# ProPrj_Ozealis_2025-07-08.net
KiCad netlist of a schematic drawn in EasyEDA Pro
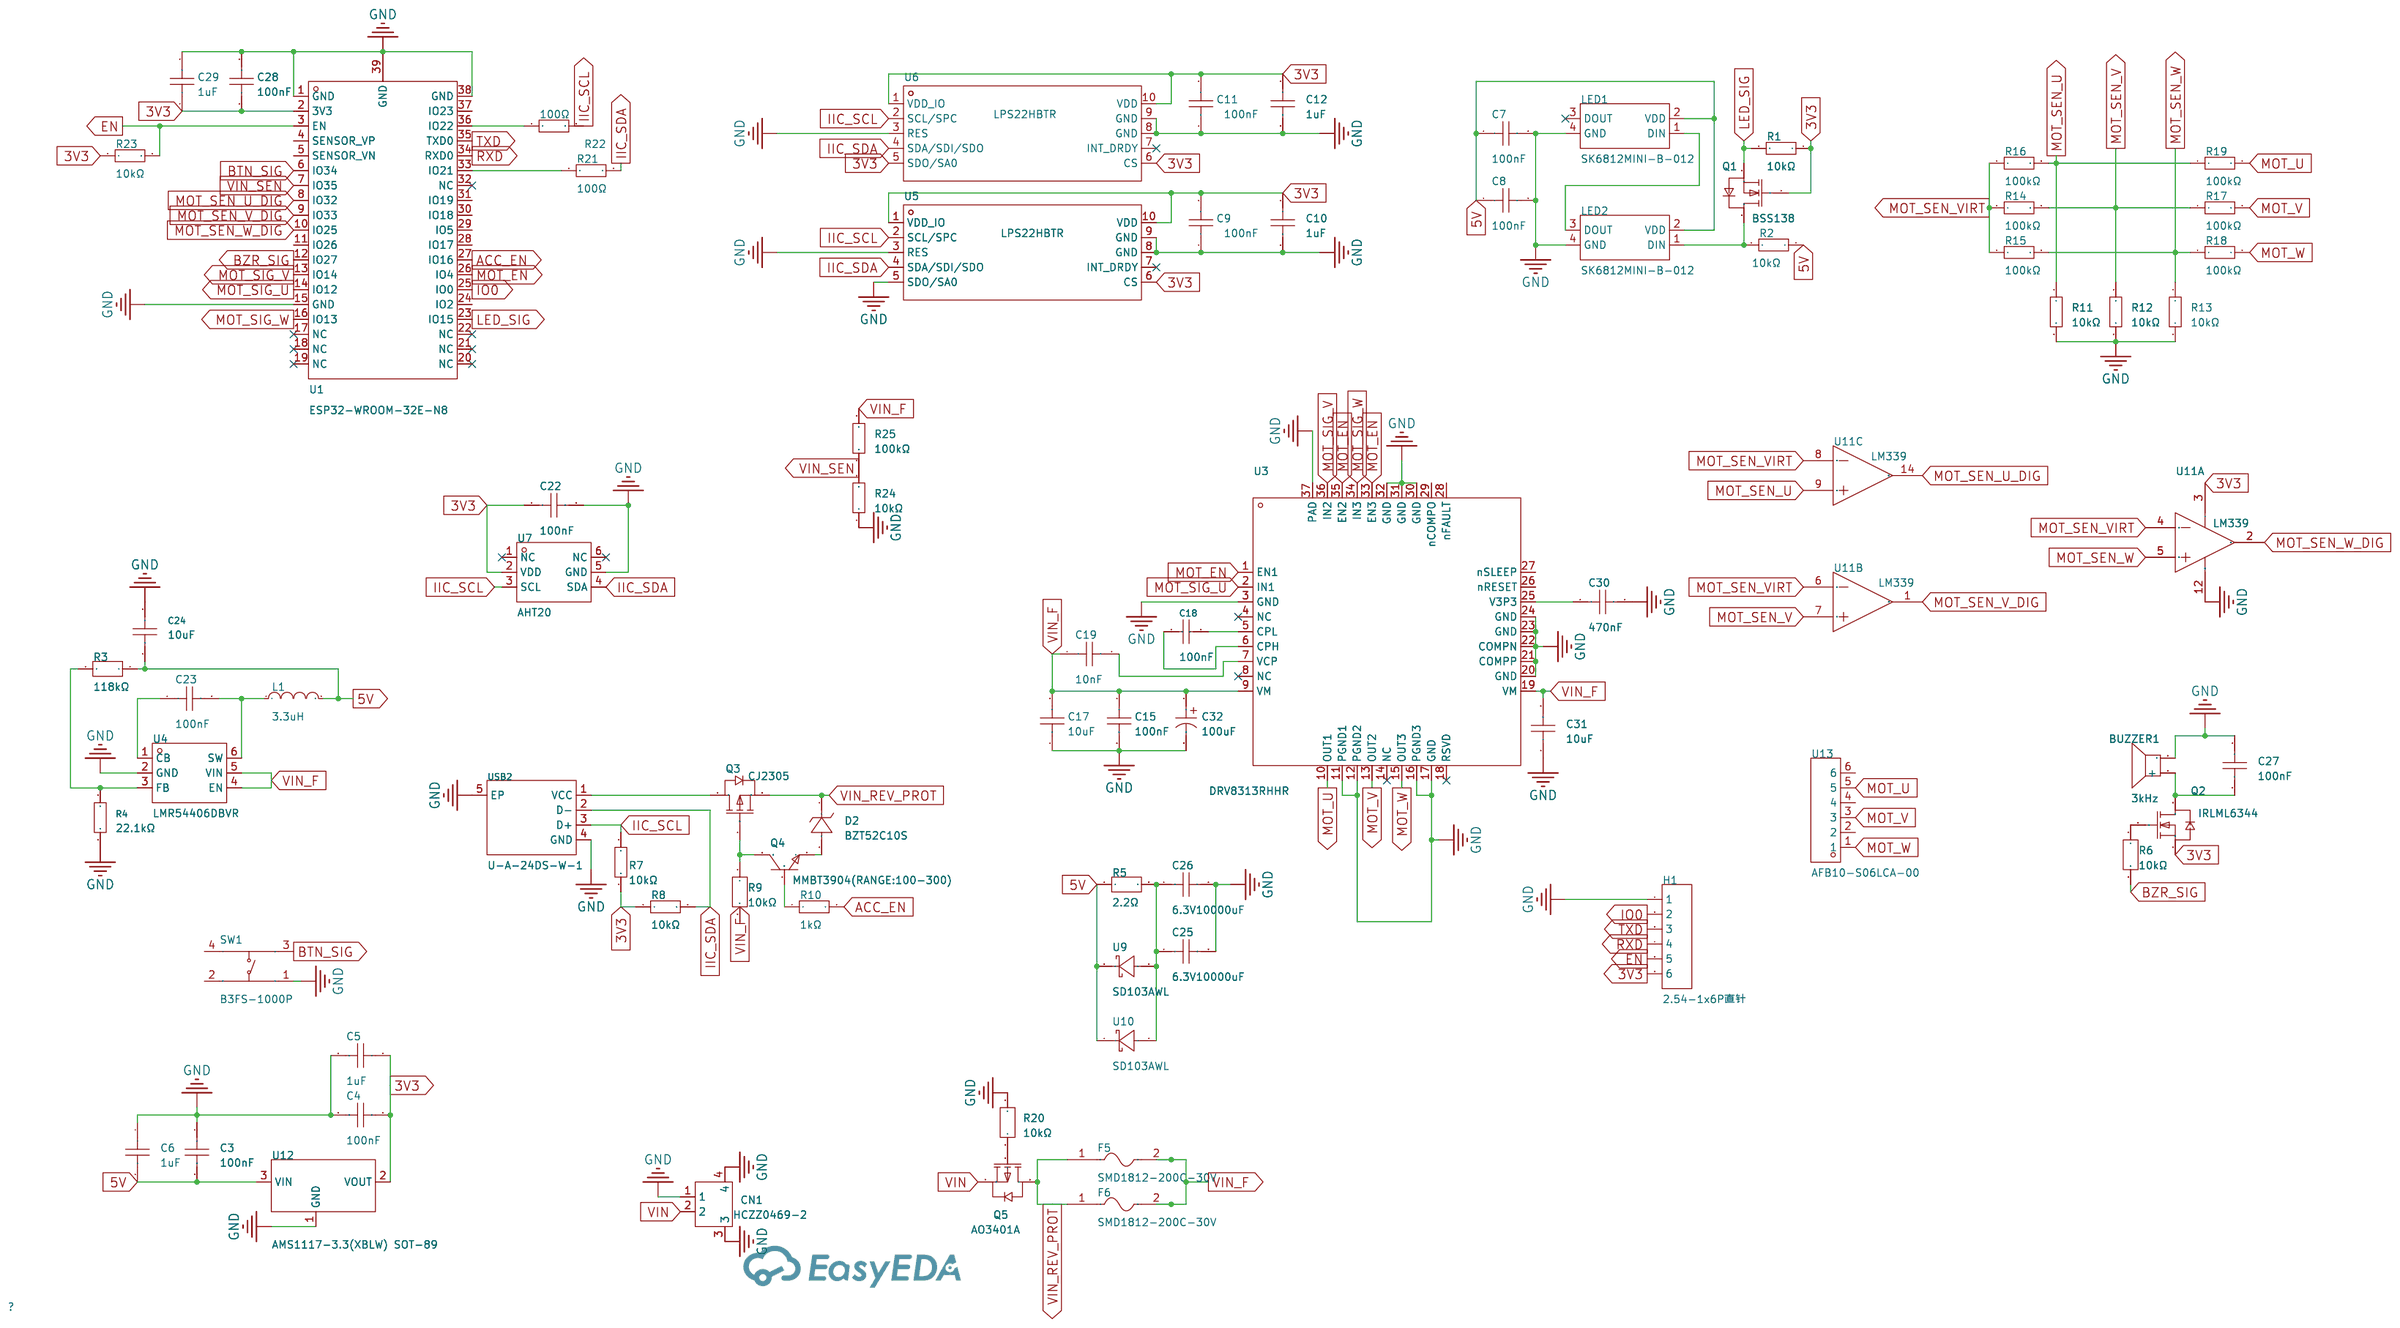
[diagram p0: schematic sheet]

(export (version "E")
  (design (tool "Eeschema 10.0.6"))
  (components
    (comp (ref "BUZZER1")
      (value "3kHz")
      (footprint "easyedapro:BUZ-SMD_L9.6-W9.6-LS10.0-R")
      (fields (field (name "Manufacturer Part") "FUET-9650B-3V") (field (name "Manufacturer") "FUET(福声科技)"))
      (libsource (lib "easyedapro") (part "FST-9650B-3V"))
    )
    (comp (ref "C3")
      (value "100nF")
      (footprint "easyedapro:C0603")
      (description "Capacitance:100nF Tolerance:±10% Tolerance:±10% Voltage Rating:50V Temperature Coefficient:X7R")
      (fields
        (field (name "Manufacturer Part") "CC0603KRX7R9BB104")
        (field (name "Manufacturer") "YAGEO(国巨)")
      )
      (libsource (lib "easyedapro") (part "CC0603KRX7R9BB104"))
    )
    (comp (ref "C4")
      (value "100nF")
      (footprint "easyedapro:C0603")
      (description "Capacitance:100nF Tolerance:±10% Tolerance:±10% Voltage Rating:50V Temperature Coefficient:X7R")
      (fields
        (field (name "Manufacturer Part") "CC0603KRX7R9BB104")
        (field (name "Manufacturer") "YAGEO(国巨)")
      )
      (libsource (lib "easyedapro") (part "CC0603KRX7R9BB104"))
    )
    (comp (ref "C5")
      (value "1uF")
      (footprint "easyedapro:C0603")
      (fields
        (field (name "Manufacturer Part") "CL10A105KB8NNNC")
        (field (name "Manufacturer") "SAMSUNG(三星)")
      )
      (libsource (lib "easyedapro") (part "CS1608Y5V105Z160NRB"))
    )
    (comp (ref "C6")
      (value "1uF")
      (footprint "easyedapro:C0603")
      (fields
        (field (name "Manufacturer Part") "CL10A105KB8NNNC")
        (field (name "Manufacturer") "SAMSUNG(三星)")
      )
      (libsource (lib "easyedapro") (part "CS1608Y5V105Z160NRB"))
    )
    (comp (ref "C7")
      (value "100nF")
      (footprint "easyedapro:C0603")
      (description "Capacitance:100nF Tolerance:±10% Tolerance:±10% Voltage Rating:50V Temperature Coefficient:X7R")
      (fields
        (field (name "Manufacturer Part") "CC0603KRX7R9BB104")
        (field (name "Manufacturer") "YAGEO(国巨)")
      )
      (libsource (lib "easyedapro") (part "CC0603KRX7R9BB104"))
    )
    (comp (ref "C8")
      (value "100nF")
      (footprint "easyedapro:C0603")
      (description "Capacitance:100nF Tolerance:±10% Tolerance:±10% Voltage Rating:50V Temperature Coefficient:X7R")
      (fields
        (field (name "Manufacturer Part") "CC0603KRX7R9BB104")
        (field (name "Manufacturer") "YAGEO(国巨)")
      )
      (libsource (lib "easyedapro") (part "CC0603KRX7R9BB104"))
    )
    (comp (ref "C9")
      (value "100nF")
      (footprint "easyedapro:C0603")
      (description "Capacitance:100nF Tolerance:±10% Tolerance:±10% Voltage Rating:50V Temperature Coefficient:X7R")
      (fields
        (field (name "Manufacturer Part") "CC0603KRX7R9BB104")
        (field (name "Manufacturer") "YAGEO(国巨)")
      )
      (libsource (lib "easyedapro") (part "CC0603KRX7R9BB104"))
    )
    (comp (ref "C10")
      (value "1uF")
      (footprint "easyedapro:C0603")
      (fields
        (field (name "Manufacturer Part") "CL10A105KB8NNNC")
        (field (name "Manufacturer") "SAMSUNG(三星)")
      )
      (libsource (lib "easyedapro") (part "CS1608Y5V105Z160NRB"))
    )
    (comp (ref "C11")
      (value "100nF")
      (footprint "easyedapro:C0603")
      (description "Capacitance:100nF Tolerance:±10% Tolerance:±10% Voltage Rating:50V Temperature Coefficient:X7R")
      (fields
        (field (name "Manufacturer Part") "CC0603KRX7R9BB104")
        (field (name "Manufacturer") "YAGEO(国巨)")
      )
      (libsource (lib "easyedapro") (part "CC0603KRX7R9BB104"))
    )
    (comp (ref "C12")
      (value "1uF")
      (footprint "easyedapro:C0603")
      (fields
        (field (name "Manufacturer Part") "CL10A105KB8NNNC")
        (field (name "Manufacturer") "SAMSUNG(三星)")
      )
      (libsource (lib "easyedapro") (part "CS1608Y5V105Z160NRB"))
    )
    (comp (ref "C15")
      (value "100nF")
      (footprint "easyedapro:C0603")
      (description "Capacitance:100nF Tolerance:±10% Tolerance:±10% Voltage Rating:50V Temperature Coefficient:X7R")
      (fields
        (field (name "Manufacturer Part") "CC0603KRX7R9BB104")
        (field (name "Manufacturer") "YAGEO(国巨)")
      )
      (libsource (lib "easyedapro") (part "CC0603KRX7R9BB104"))
    )
    (comp (ref "C17")
      (value "10uF")
      (footprint "easyedapro:C0805")
      (fields
        (field (name "Manufacturer Part") "GRM21BR61H106KE43L")
        (field (name "Manufacturer") "muRata(村田)")
      )
      (libsource (lib "easyedapro") (part "GRM21BR61H106KE43L"))
    )
    (comp (ref "C18")
      (value "100nF")
      (footprint "easyedapro:C0402")
      (description "Capacitance:100nF Tolerance:±10% Tolerance:±10% Voltage Rating:50V Temperature Coefficient:X7R")
      (fields
        (field (name "Manufacturer Part") "CC0603KRX7R9BB104")
        (field (name "Manufacturer") "YAGEO(国巨)")
      )
      (libsource (lib "easyedapro") (part "CC0402KRX7R9BB103"))
    )
    (comp (ref "C19")
      (value "10nF")
      (footprint "easyedapro:C0402")
      (description "Capacitance:10nF Tolerance:±10% Tolerance:±10% Voltage Rating:50V Temperature Coefficient:X7R")
      (fields (field (name "Manufacturer Part") "0603B103K500NT") (field (name "Manufacturer") "FH(风华)"))
      (libsource (lib "easyedapro") (part "FCC0402B104K160AT"))
    )
    (comp (ref "C22")
      (value "100nF")
      (footprint "easyedapro:C0603")
      (description "Capacitance:100nF Tolerance:±10% Tolerance:±10% Voltage Rating:50V Temperature Coefficient:X7R")
      (fields
        (field (name "Manufacturer Part") "CC0603KRX7R9BB104")
        (field (name "Manufacturer") "YAGEO(国巨)")
      )
      (libsource (lib "easyedapro") (part "CC0603KRX7R9BB104"))
    )
    (comp (ref "C23")
      (value "100nF")
      (footprint "easyedapro:C0603")
      (description "Capacitance:100nF Tolerance:±10% Tolerance:±10% Voltage Rating:50V Temperature Coefficient:X7R")
      (fields
        (field (name "Manufacturer Part") "CC0603KRX7R9BB104")
        (field (name "Manufacturer") "YAGEO(国巨)")
      )
      (libsource (lib "easyedapro") (part "CC0603KRX7R9BB104"))
    )
    (comp (ref "C24")
      (value "10uF")
      (footprint "easyedapro:C0603")
      (fields
        (field (name "Manufacturer Part") "TCC0603X5R106M6R3CT")
        (field (name "Manufacturer") "CCTC(三环)")
      )
      (libsource (lib "easyedapro") (part "TCC0603X5R106M6R3CT"))
    )
    (comp (ref "C25")
      (value "6.3V10000uF")
      (footprint "easyedapro:C0603")
      (libsource (lib "easyedapro") (part "CAP"))
    )
    (comp (ref "C26")
      (value "6.3V10000uF")
      (footprint "easyedapro:C0603")
      (libsource (lib "easyedapro") (part "CAP"))
    )
    (comp (ref "C27")
      (value "100nF")
      (footprint "easyedapro:C0603")
      (description "Capacitance:100nF Tolerance:±10% Tolerance:±10% Voltage Rating:50V Temperature Coefficient:X7R")
      (fields
        (field (name "Manufacturer Part") "CC0603KRX7R9BB104")
        (field (name "Manufacturer") "YAGEO(国巨)")
      )
      (libsource (lib "easyedapro") (part "CC0603KRX7R9BB104"))
    )
    (comp (ref "C28")
      (value "100nF")
      (footprint "easyedapro:C0603")
      (description "Capacitance:100nF Tolerance:±10% Tolerance:±10% Voltage Rating:50V Temperature Coefficient:X7R")
      (fields
        (field (name "Manufacturer Part") "CC0603KRX7R9BB104")
        (field (name "Manufacturer") "YAGEO(国巨)")
      )
      (libsource (lib "easyedapro") (part "CC0603KRX7R9BB104"))
    )
    (comp (ref "C29")
      (value "1uF")
      (footprint "easyedapro:C0603")
      (fields
        (field (name "Manufacturer Part") "CL10A105KB8NNNC")
        (field (name "Manufacturer") "SAMSUNG(三星)")
      )
      (libsource (lib "easyedapro") (part "CS1608Y5V105Z160NRB"))
    )
    (comp (ref "C30")
      (value "470nF")
      (footprint "easyedapro:C0603")
      (fields
        (field (name "Manufacturer Part") "CL10B474KA8NNNC")
        (field (name "Manufacturer") "SAMSUNG(三星)")
      )
      (libsource (lib "easyedapro") (part "CC0603KRX7R9BB474"))
    )
    (comp (ref "C31")
      (value "10uF")
      (footprint "easyedapro:C0805")
      (fields
        (field (name "Manufacturer Part") "GRM21BR61H106KE43L")
        (field (name "Manufacturer") "muRata(村田)")
      )
      (libsource (lib "easyedapro") (part "GRM21BR61H106KE43L"))
    )
    (comp (ref "C32")
      (value "100uF")
      (footprint "easyedapro:CAP-SMD_BD6.3-L6.6-W6.6-LS7.4-FD")
      (fields
        (field (name "Manufacturer Part") "RVT100UF35V67RV0034")
        (field (name "Manufacturer") "KNSCHA(科尼盛)")
      )
      (libsource (lib "easyedapro") (part "RVT100UF35V67RV0034"))
    )
    (comp (ref "CN1")
      (value "HCZZ0469-2")
      (footprint "easyedapro:CONN-SMD_2P-P2.00_HCZZ0469-2")
      (fields (field (name "Manufacturer") "HC(虹成电子)"))
      (libsource (lib "easyedapro") (part "HCZZ0469-2"))
    )
    (comp (ref "D2")
      (value "BZT52C10S")
      (footprint "easyedapro:SOD-323_L1.7-W1.3-LS2.6-RD")
      (fields (field (name "Manufacturer") "宏嘉诚"))
      (libsource (lib "easyedapro") (part "BZT52C10S_C19077446"))
    )
    (comp (ref "F5")
      (value "SMD1812-200C-30V")
      (footprint "easyedapro:F1812")
      (fields (field (name "Manufacturer") "BNstar(比诺星)"))
      (libsource (lib "easyedapro") (part "SMD1812-200C-30V"))
    )
    (comp (ref "F6")
      (value "SMD1812-200C-30V")
      (footprint "easyedapro:F1812")
      (fields (field (name "Manufacturer") "BNstar(比诺星)"))
      (libsource (lib "easyedapro") (part "SMD1812-200C-30V"))
    )
    (comp (ref "H1")
      (value "2.54-1x6P直针")
      (footprint "easyedapro:HDR-TH_6P-P2.54-V-M-1")
      (fields (field (name "Manufacturer") "BOOMELE(博穆精密)"))
      (libsource (lib "easyedapro") (part "Header-Male-2.54_1x6"))
    )
    (comp (ref "L1")
      (value "3.3uH")
      (footprint "easyedapro:IND-SMD_L3.0-W3.0_FNR30XXS")
      (fields (field (name "Manufacturer Part") "FNR3015S3R3MT") (field (name "Manufacturer") "cjiang(长江微电)"))
      (libsource (lib "easyedapro") (part "FNR3015S3R3MT"))
    )
    (comp (ref "LED1")
      (value "SK6812MINI-B-012")
      (footprint "easyedapro:LED-SMD_4P-L3.5-W3.5-R-SK6812MINI")
      (fields (field (name "Manufacturer") "欧思科光电"))
      (libsource (lib "easyedapro") (part "SK6812MINI-B-012"))
    )
    (comp (ref "LED2")
      (value "SK6812MINI-B-012")
      (footprint "easyedapro:LED-SMD_4P-L3.5-W3.5-R-SK6812MINI")
      (fields (field (name "Manufacturer") "欧思科光电"))
      (libsource (lib "easyedapro") (part "SK6812MINI-B-012"))
    )
    (comp (ref "Q1")
      (value "BSS138")
      (footprint "easyedapro:SOT-23-3_L2.9-W1.3-P1.90-LS2.4-BR-1")
      (fields (field (name "Manufacturer") "KUU"))
      (libsource (lib "easyedapro") (part "BSS138_C3015220"))
    )
    (comp (ref "Q2")
      (value "IRLML6344")
      (footprint "easyedapro:SOT-23-3_L3.0-W1.7-P0.95-LS2.9-BR")
      (fields (field (name "Manufacturer") "Hottech(合科泰)"))
      (libsource (lib "easyedapro") (part "IRLML6344"))
    )
    (comp (ref "Q3")
      (value "CJ2305")
      (footprint "easyedapro:SOT-23-3_L2.9-W1.3-P1.90-LS2.4-BR")
      (fields (field (name "Manufacturer") "CJ(江苏长电/长晶)"))
      (libsource (lib "easyedapro") (part "CJ2305"))
    )
    (comp (ref "Q4")
      (value "MMBT3904(RANGE:100-300)")
      (footprint "easyedapro:SOT-23-3_L2.9-W1.3-P1.90-LS2.4-BR")
      (fields (field (name "Manufacturer") "CJ(江苏长电/长晶)"))
      (libsource (lib "easyedapro") (part "MMBT3904"))
    )
    (comp (ref "Q5")
      (value "AO3401A")
      (footprint "easyedapro:SOT-23_L2.9-W1.3-P1.90-LS2.4-BR")
      (fields (field (name "Manufacturer") "UMW(友台半导体)"))
      (libsource (lib "easyedapro") (part "AO3401A_C347476"))
    )
    (comp (ref "R1")
      (value "10kΩ")
      (footprint "easyedapro:R0603")
      (fields (field (name "Manufacturer Part") "RC0603FR-0710KL") (field (name "Manufacturer") "YAGEO(国巨)"))
      (libsource (lib "easyedapro") (part "RC0603FR-0710KL"))
    )
    (comp (ref "R2")
      (value "10kΩ")
      (footprint "easyedapro:R0603")
      (fields (field (name "Manufacturer Part") "RC0603FR-0710KL") (field (name "Manufacturer") "YAGEO(国巨)"))
      (libsource (lib "easyedapro") (part "RC0603FR-0710KL"))
    )
    (comp (ref "R3")
      (value "118kΩ")
      (footprint "easyedapro:R0402")
      (fields (field (name "Manufacturer Part") "RC0402FR-07118KL") (field (name "Manufacturer") "YAGEO(国巨)"))
      (libsource (lib "easyedapro") (part "RC0402FR-07118KL"))
    )
    (comp (ref "R4")
      (value "22.1kΩ")
      (footprint "easyedapro:R0402")
      (fields
        (field (name "Manufacturer Part") "RMC040222.1K1%N")
        (field (name "Manufacturer") "Tyohm(幸亚电阻)")
      )
      (libsource (lib "easyedapro") (part "RMC040222.1K1%N"))
    )
    (comp (ref "R5")
      (value "2.2Ω")
      (footprint "easyedapro:R0603")
      (fields (field (name "Manufacturer Part") "FRC0603J2R2TS") (field (name "Manufacturer") "FOJAN(富捷)"))
      (libsource (lib "easyedapro") (part "FRC0603J2R2TS"))
    )
    (comp (ref "R6")
      (value "10kΩ")
      (footprint "easyedapro:R0603")
      (fields (field (name "Manufacturer Part") "FRC0603J103 TS") (field (name "Manufacturer") "FOJAN(富捷)"))
      (libsource (lib "easyedapro") (part "FRC0603J103TS"))
    )
    (comp (ref "R7")
      (value "10kΩ")
      (footprint "easyedapro:R0603")
      (fields (field (name "Manufacturer Part") "FRC0603J103 TS") (field (name "Manufacturer") "FOJAN(富捷)"))
      (libsource (lib "easyedapro") (part "RC0603FR-074K7L"))
    )
    (comp (ref "R8")
      (value "10kΩ")
      (footprint "easyedapro:R0603")
      (fields (field (name "Manufacturer Part") "FRC0603J103 TS") (field (name "Manufacturer") "FOJAN(富捷)"))
      (libsource (lib "easyedapro") (part "RC0603FR-074K7L"))
    )
    (comp (ref "R9")
      (value "10kΩ")
      (footprint "easyedapro:R0603")
      (fields (field (name "Manufacturer Part") "FRC0603J103 TS") (field (name "Manufacturer") "FOJAN(富捷)"))
      (libsource (lib "easyedapro") (part "FRC0603J103TS"))
    )
    (comp (ref "R10")
      (value "1kΩ")
      (footprint "easyedapro:R0603")
      (fields
        (field (name "Manufacturer Part") "0603WAF1001T5E")
        (field (name "Manufacturer") "UNI-ROYAL(厚声)")
      )
      (libsource (lib "easyedapro") (part "0603WAF1001T5E"))
    )
    (comp (ref "R11")
      (value "10kΩ")
      (footprint "easyedapro:R0603")
      (fields (field (name "Manufacturer Part") "RC0603FR-0710KL") (field (name "Manufacturer") "YAGEO(国巨)"))
      (libsource (lib "easyedapro") (part "RC0603FR-0710KL"))
    )
    (comp (ref "R12")
      (value "10kΩ")
      (footprint "easyedapro:R0603")
      (fields (field (name "Manufacturer Part") "RC0603FR-0710KL") (field (name "Manufacturer") "YAGEO(国巨)"))
      (libsource (lib "easyedapro") (part "RC0603FR-0710KL"))
    )
    (comp (ref "R13")
      (value "10kΩ")
      (footprint "easyedapro:R0603")
      (fields (field (name "Manufacturer Part") "RC0603FR-0710KL") (field (name "Manufacturer") "YAGEO(国巨)"))
      (libsource (lib "easyedapro") (part "RC0603FR-0710KL"))
    )
    (comp (ref "R14")
      (value "100kΩ")
      (footprint "easyedapro:R0603")
      (fields
        (field (name "Manufacturer Part") "0603WAF1003T5E")
        (field (name "Manufacturer") "UNI-ROYAL(厚声)")
      )
      (libsource (lib "easyedapro") (part "0603WAF1003T5E"))
    )
    (comp (ref "R15")
      (value "100kΩ")
      (footprint "easyedapro:R0603")
      (fields
        (field (name "Manufacturer Part") "0603WAF1003T5E")
        (field (name "Manufacturer") "UNI-ROYAL(厚声)")
      )
      (libsource (lib "easyedapro") (part "0603WAF1003T5E"))
    )
    (comp (ref "R16")
      (value "100kΩ")
      (footprint "easyedapro:R0603")
      (fields
        (field (name "Manufacturer Part") "0603WAF1003T5E")
        (field (name "Manufacturer") "UNI-ROYAL(厚声)")
      )
      (libsource (lib "easyedapro") (part "0603WAF1003T5E"))
    )
    (comp (ref "R17")
      (value "100kΩ")
      (footprint "easyedapro:R0603")
      (fields
        (field (name "Manufacturer Part") "0603WAF1003T5E")
        (field (name "Manufacturer") "UNI-ROYAL(厚声)")
      )
      (libsource (lib "easyedapro") (part "0603WAF1003T5E"))
    )
    (comp (ref "R18")
      (value "100kΩ")
      (footprint "easyedapro:R0603")
      (fields
        (field (name "Manufacturer Part") "0603WAF1003T5E")
        (field (name "Manufacturer") "UNI-ROYAL(厚声)")
      )
      (libsource (lib "easyedapro") (part "0603WAF1003T5E"))
    )
    (comp (ref "R19")
      (value "100kΩ")
      (footprint "easyedapro:R0603")
      (fields
        (field (name "Manufacturer Part") "0603WAF1003T5E")
        (field (name "Manufacturer") "UNI-ROYAL(厚声)")
      )
      (libsource (lib "easyedapro") (part "0603WAF1003T5E"))
    )
    (comp (ref "R20")
      (value "10kΩ")
      (footprint "easyedapro:R0603")
      (fields (field (name "Manufacturer Part") "FRC0603J103 TS") (field (name "Manufacturer") "FOJAN(富捷)"))
      (libsource (lib "easyedapro") (part "FRC0603J103TS"))
    )
    (comp (ref "R21")
      (value "100Ω")
      (footprint "easyedapro:R0603")
      (fields
        (field (name "Manufacturer Part") "0603WAF1000T5E")
        (field (name "Manufacturer") "UNI-ROYAL(厚声)")
      )
      (libsource (lib "easyedapro") (part "0603WAF1000T5E"))
    )
    (comp (ref "R22")
      (value "100Ω")
      (footprint "easyedapro:R0603")
      (fields
        (field (name "Manufacturer Part") "0603WAF1000T5E")
        (field (name "Manufacturer") "UNI-ROYAL(厚声)")
      )
      (libsource (lib "easyedapro") (part "0603WAF1000T5E"))
    )
    (comp (ref "R23")
      (value "10kΩ")
      (footprint "easyedapro:R0603")
      (fields (field (name "Manufacturer Part") "FRC0603J103 TS") (field (name "Manufacturer") "FOJAN(富捷)"))
      (libsource (lib "easyedapro") (part "RC0603FR-074K7L"))
    )
    (comp (ref "R24")
      (value "10kΩ")
      (footprint "easyedapro:R0603")
      (fields (field (name "Manufacturer Part") "FRC0603J103 TS") (field (name "Manufacturer") "FOJAN(富捷)"))
      (libsource (lib "easyedapro") (part "RC0603FR-074K7L"))
    )
    (comp (ref "R25")
      (value "100kΩ")
      (footprint "easyedapro:R0603")
      (fields
        (field (name "Manufacturer Part") "0603WAF1003T5E")
        (field (name "Manufacturer") "UNI-ROYAL(厚声)")
      )
      (libsource (lib "easyedapro") (part "0603WAF1003T5E"))
    )
    (comp (ref "SW1")
      (value "B3FS-1000P")
      (footprint "easyedapro:KEY-SMD_4P-L6.0-W6.3-P4.50-LS8.0")
      (fields (field (name "Manufacturer") "OMRON(欧姆龙)"))
      (libsource (lib "easyedapro") (part "B3FS-1000P"))
    )
    (comp (ref "U1")
      (value "ESP32-WROOM-32E-N8")
      (footprint "easyedapro:WIFI-SMD_ESP32-WROOM-32E")
      (fields (field (name "Manufacturer") "ESPRESSIF(乐鑫)"))
      (libsource (lib "easyedapro") (part "ESP32-WROOM-32E(8MB)"))
    )
    (comp (ref "U3")
      (value "DRV8313RHHR")
      (footprint "easyedapro:VQFN-36_L6.0-W6.0-P0.50-TL-EP")
      (fields (field (name "Manufacturer") "TI(德州仪器)"))
      (libsource (lib "easyedapro") (part "DRV8313RHHR"))
    )
    (comp (ref "U4")
      (value "LMR54406DBVR")
      (footprint "easyedapro:SOT-23-6_L2.9-W1.6-P0.95-LS2.8-BR")
      (fields (field (name "Manufacturer") "TI(德州仪器)"))
      (libsource (lib "easyedapro") (part "LMR54406DBVR"))
    )
    (comp (ref "U5")
      (value "LPS22HBTR")
      (footprint "easyedapro:HLGA-10L_LPS22HBTR")
      (fields (field (name "Manufacturer") "ST(意法半导体)"))
      (libsource (lib "easyedapro") (part "LPS22HBTR"))
    )
    (comp (ref "U6")
      (value "LPS22HBTR")
      (footprint "easyedapro:HLGA-10L_LPS22HBTR")
      (fields (field (name "Manufacturer") "ST(意法半导体)"))
      (libsource (lib "easyedapro") (part "LPS22HBTR"))
    )
    (comp (ref "U7")
      (value "AHT20")
      (footprint "easyedapro:SENSOR-SMD_L3.0-W3.0-P1.00-BR")
      (fields (field (name "Manufacturer") "广州奥松"))
      (libsource (lib "easyedapro") (part "AHT20_C2757850"))
    )
    (comp (ref "U9")
      (value "SD103AWL")
      (footprint "easyedapro:SOD-123FL_L2.8-W1.9-LS3.7-RD")
      (fields (field (name "Manufacturer") "GOODWORK(固得沃克)"))
      (libsource (lib "easyedapro") (part "SD103AWL"))
    )
    (comp (ref "U10")
      (value "SD103AWL")
      (footprint "easyedapro:SOD-123FL_L2.8-W1.9-LS3.7-RD")
      (fields (field (name "Manufacturer") "GOODWORK(固得沃克)"))
      (libsource (lib "easyedapro") (part "SD103AWL"))
    )
    (comp (ref "U11")
      (value "LM339")
      (footprint "easyedapro:SOIC-14_L8.7-W3.9-P1.27-LS6.0-BL")
      (fields (field (name "Manufacturer") "JSMSEMI(杰盛微)"))
      (libsource (lib "easyedapro") (part "LM339_C5456631"))
    )
    (comp (ref "U12")
      (value "AMS1117-3.3(XBLW) SOT-89")
      (footprint "easyedapro:SOT-89-3_L4.5-W2.5-P1.50-LS4.2-BR")
      (fields (field (name "Manufacturer") "XBLW(芯伯乐)"))
      (libsource (lib "easyedapro") (part "AMS1117-3.3(XBLW)"))
    )
    (comp (ref "U13")
      (value "AFB10-S06LCA-00")
      (footprint "easyedapro:FPC-SMD_6P-P1.00_AFB10-S6LCA-00")
      (fields (field (name "Manufacturer") "JS(钜硕电子)"))
      (libsource (lib "easyedapro") (part "AFB10-S06LCA-00"))
    )
    (comp (ref "USB2")
      (value "U-A-24DS-W-1")
      (footprint "easyedapro:USB-A-SMD_U-A-24DS-W-1.")
      (fields (field (name "Manufacturer") "韩国韩荣"))
      (libsource (lib "easyedapro") (part "U-A-24DS-W-1"))
    )
  )
  (nets
    (net (code "1") (name "3V3") (class "Default")
      (node (ref "C10") (pin "1") (pinfunction "1_1") (pintype "unspecified"))
      (node (ref "C11") (pin "2") (pinfunction "2_2") (pintype "unspecified"))
      (node (ref "C12") (pin "1") (pinfunction "1_1") (pintype "unspecified"))
      (node (ref "C22") (pin "1") (pinfunction "1_1") (pintype "unspecified"))
      (node (ref "C28") (pin "1") (pinfunction "1_1") (pintype "unspecified"))
      (node (ref "C29") (pin "1") (pinfunction "1_1") (pintype "unspecified"))
      (node (ref "C4") (pin "1") (pinfunction "1_1") (pintype "unspecified"))
      (node (ref "C5") (pin "1") (pinfunction "1_1") (pintype "unspecified"))
      (node (ref "C9") (pin "2") (pinfunction "2_2") (pintype "unspecified"))
      (node (ref "H1") (pin "6") (pinfunction "6_6") (pintype "input"))
      (node (ref "Q1") (pin "1") (pinfunction "G_1") (pintype "unspecified"))
      (node (ref "Q2") (pin "2") (pinfunction "S_2") (pintype "unspecified"))
      (node (ref "R1") (pin "1") (pinfunction "1_1") (pintype "input"))
      (node (ref "R23") (pin "1") (pinfunction "1_1") (pintype "input"))
      (node (ref "R7") (pin "1") (pinfunction "1_1") (pintype "input"))
      (node (ref "R8") (pin "1") (pinfunction "1_1") (pintype "input"))
      (node (ref "U1") (pin "2") (pinfunction "3V3_2") (pintype "unspecified"))
      (node (ref "U11") (pin "3") (pinfunction "V+_3") (pintype "unspecified"))
      (node (ref "U12") (pin "2") (pinfunction "VOUT_2") (pintype "unspecified"))
      (node (ref "U5") (pin "1") (pinfunction "VDD_IO_1") (pintype "unspecified"))
      (node (ref "U5") (pin "10") (pinfunction "VDD_10") (pintype "unspecified"))
      (node (ref "U5") (pin "6") (pinfunction "CS_6") (pintype "unspecified"))
      (node (ref "U6") (pin "1") (pinfunction "VDD_IO_1") (pintype "unspecified"))
      (node (ref "U6") (pin "10") (pinfunction "VDD_10") (pintype "unspecified"))
      (node (ref "U6") (pin "5") (pinfunction "SDO/SA0_5") (pintype "unspecified"))
      (node (ref "U6") (pin "6") (pinfunction "CS_6") (pintype "unspecified"))
      (node (ref "U7") (pin "2") (pinfunction "VDD_2") (pintype "unspecified"))
    )
    (net (code "2") (name "5V") (class "Default")
      (node (ref "C24") (pin "1") (pinfunction "1_1") (pintype "input"))
      (node (ref "C3") (pin "2") (pinfunction "2_2") (pintype "unspecified"))
      (node (ref "C6") (pin "2") (pinfunction "2_2") (pintype "unspecified"))
      (node (ref "C7") (pin "1") (pinfunction "1_1") (pintype "unspecified"))
      (node (ref "C8") (pin "1") (pinfunction "1_1") (pintype "unspecified"))
      (node (ref "L1") (pin "2") (pinfunction "2_2") (pintype "unspecified"))
      (node (ref "LED1") (pin "2") (pinfunction "VDD_2") (pintype "unspecified"))
      (node (ref "LED2") (pin "2") (pinfunction "VDD_2") (pintype "unspecified"))
      (node (ref "R2") (pin "1") (pinfunction "1_1") (pintype "input"))
      (node (ref "R3") (pin "1") (pinfunction "1_1") (pintype "unspecified"))
      (node (ref "R5") (pin "1") (pinfunction "1_1") (pintype "unspecified"))
      (node (ref "U10") (pin "1") (pinfunction "K_1") (pintype "unspecified"))
      (node (ref "U12") (pin "3") (pinfunction "VIN_3") (pintype "unspecified"))
      (node (ref "U9") (pin "1") (pinfunction "K_1") (pintype "unspecified"))
    )
    (net (code "3") (name "ACC_EN") (class "Default")
      (node (ref "R10") (pin "2") (pinfunction "2_2") (pintype "input"))
      (node (ref "U1") (pin "27") (pinfunction "IO16_27") (pintype "unspecified"))
    )
    (net (code "4") (name "BTN_SIG") (class "Default")
      (node (ref "SW1") (pin "3") (pinfunction "3_3") (pintype "unspecified"))
      (node (ref "U1") (pin "6") (pinfunction "IO34_6") (pintype "unspecified"))
    )
    (net (code "5") (name "BZR_SIG") (class "Default")
      (node (ref "R6") (pin "1") (pinfunction "1_1") (pintype "unspecified"))
      (node (ref "U1") (pin "12") (pinfunction "IO27_12") (pintype "unspecified"))
    )
    (net (code "6") (name "EN") (class "Default")
      (node (ref "H1") (pin "5") (pinfunction "5_5") (pintype "input"))
      (node (ref "R23") (pin "2") (pinfunction "2_2") (pintype "input"))
      (node (ref "U1") (pin "3") (pinfunction "EN_3") (pintype "unspecified"))
    )
    (net (code "7") (name "GND") (class "Default")
      (node (ref "BUZZER1") (pin "2") (pinfunction "2_2") (pintype "unspecified"))
      (node (ref "C10") (pin "2") (pinfunction "2_2") (pintype "unspecified"))
      (node (ref "C11") (pin "1") (pinfunction "1_1") (pintype "unspecified"))
      (node (ref "C12") (pin "2") (pinfunction "2_2") (pintype "unspecified"))
      (node (ref "C15") (pin "2") (pinfunction "2_2") (pintype "unspecified"))
      (node (ref "C17") (pin "1") (pinfunction "1_1") (pintype "unspecified"))
      (node (ref "C22") (pin "2") (pinfunction "2_2") (pintype "unspecified"))
      (node (ref "C24") (pin "2") (pinfunction "2_2") (pintype "input"))
      (node (ref "C25") (pin "2") (pinfunction "2_2") (pintype "input"))
      (node (ref "C26") (pin "2") (pinfunction "2_2") (pintype "input"))
      (node (ref "C27") (pin "1") (pinfunction "1_1") (pintype "unspecified"))
      (node (ref "C28") (pin "2") (pinfunction "2_2") (pintype "unspecified"))
      (node (ref "C29") (pin "2") (pinfunction "2_2") (pintype "unspecified"))
      (node (ref "C3") (pin "1") (pinfunction "1_1") (pintype "unspecified"))
      (node (ref "C30") (pin "2") (pinfunction "2_2") (pintype "unspecified"))
      (node (ref "C31") (pin "1") (pinfunction "1_1") (pintype "unspecified"))
      (node (ref "C32") (pin "2") (pinfunction "2_2") (pintype "input"))
      (node (ref "C4") (pin "2") (pinfunction "2_2") (pintype "unspecified"))
      (node (ref "C5") (pin "2") (pinfunction "2_2") (pintype "unspecified"))
      (node (ref "C6") (pin "1") (pinfunction "1_1") (pintype "unspecified"))
      (node (ref "C7") (pin "2") (pinfunction "2_2") (pintype "unspecified"))
      (node (ref "C8") (pin "2") (pinfunction "2_2") (pintype "unspecified"))
      (node (ref "C9") (pin "1") (pinfunction "1_1") (pintype "unspecified"))
      (node (ref "CN1") (pin "1") (pinfunction "1_1") (pintype "unspecified"))
      (node (ref "CN1") (pin "3") (pinfunction "3_3") (pintype "unspecified"))
      (node (ref "CN1") (pin "4") (pinfunction "4_4") (pintype "unspecified"))
      (node (ref "H1") (pin "1") (pinfunction "1_1") (pintype "input"))
      (node (ref "LED1") (pin "4") (pinfunction "GND_4") (pintype "unspecified"))
      (node (ref "LED2") (pin "4") (pinfunction "GND_4") (pintype "unspecified"))
      (node (ref "R11") (pin "2") (pinfunction "2_2") (pintype "input"))
      (node (ref "R12") (pin "2") (pinfunction "2_2") (pintype "input"))
      (node (ref "R13") (pin "2") (pinfunction "2_2") (pintype "input"))
      (node (ref "R20") (pin "2") (pinfunction "2_2") (pintype "unspecified"))
      (node (ref "R24") (pin "1") (pinfunction "1_1") (pintype "input"))
      (node (ref "R4") (pin "1") (pinfunction "1_1") (pintype "input"))
      (node (ref "SW1") (pin "1") (pinfunction "1_1") (pintype "unspecified"))
      (node (ref "U1") (pin "1") (pinfunction "GND_1") (pintype "unspecified"))
      (node (ref "U1") (pin "15") (pinfunction "GND_15") (pintype "unspecified"))
      (node (ref "U1") (pin "38") (pinfunction "GND_38") (pintype "unspecified"))
      (node (ref "U1") (pin "39") (pinfunction "GND_39") (pintype "unspecified"))
      (node (ref "U11") (pin "12") (pinfunction "GND_12") (pintype "unspecified"))
      (node (ref "U12") (pin "1") (pinfunction "GND_1") (pintype "unspecified"))
      (node (ref "U3") (pin "11") (pinfunction "PGND1_11") (pintype "unspecified"))
      (node (ref "U3") (pin "12") (pinfunction "PGND2_12") (pintype "unspecified"))
      (node (ref "U3") (pin "16") (pinfunction "PGND3_16") (pintype "unspecified"))
      (node (ref "U3") (pin "17") (pinfunction "GND_17") (pintype "unspecified"))
      (node (ref "U3") (pin "20") (pinfunction "GND_20") (pintype "unspecified"))
      (node (ref "U3") (pin "21") (pinfunction "COMPP_21") (pintype "unspecified"))
      (node (ref "U3") (pin "22") (pinfunction "COMPN_22") (pintype "unspecified"))
      (node (ref "U3") (pin "23") (pinfunction "GND_23") (pintype "unspecified"))
      (node (ref "U3") (pin "24") (pinfunction "GND_24") (pintype "unspecified"))
      (node (ref "U3") (pin "3") (pinfunction "GND_3") (pintype "unspecified"))
      (node (ref "U3") (pin "30") (pinfunction "GND_30") (pintype "unspecified"))
      (node (ref "U3") (pin "31") (pinfunction "GND_31") (pintype "unspecified"))
      (node (ref "U3") (pin "32") (pinfunction "GND_32") (pintype "unspecified"))
      (node (ref "U3") (pin "37") (pinfunction "PAD_37") (pintype "unspecified"))
      (node (ref "U4") (pin "2") (pinfunction "GND_2") (pintype "unspecified"))
      (node (ref "U5") (pin "3") (pinfunction "RES_3") (pintype "unspecified"))
      (node (ref "U5") (pin "5") (pinfunction "SDO/SA0_5") (pintype "unspecified"))
      (node (ref "U5") (pin "8") (pinfunction "GND_8") (pintype "unspecified"))
      (node (ref "U5") (pin "9") (pinfunction "GND_9") (pintype "unspecified"))
      (node (ref "U6") (pin "3") (pinfunction "RES_3") (pintype "unspecified"))
      (node (ref "U6") (pin "8") (pinfunction "GND_8") (pintype "unspecified"))
      (node (ref "U6") (pin "9") (pinfunction "GND_9") (pintype "unspecified"))
      (node (ref "U7") (pin "5") (pinfunction "GND_5") (pintype "unspecified"))
      (node (ref "USB2") (pin "4") (pinfunction "GND_4") (pintype "input"))
      (node (ref "USB2") (pin "5") (pinfunction "EP_5") (pintype "input"))
    )
    (net (code "8") (name "IIC_SCL") (class "Default")
      (node (ref "R22") (pin "2") (pinfunction "2_2") (pintype "input"))
      (node (ref "R7") (pin "2") (pinfunction "2_2") (pintype "input"))
      (node (ref "U5") (pin "2") (pinfunction "SCL/SPC_2") (pintype "unspecified"))
      (node (ref "U6") (pin "2") (pinfunction "SCL/SPC_2") (pintype "unspecified"))
      (node (ref "U7") (pin "3") (pinfunction "SCL_3") (pintype "unspecified"))
      (node (ref "USB2") (pin "3") (pinfunction "D+_3") (pintype "input"))
    )
    (net (code "9") (name "IIC_SDA") (class "Default")
      (node (ref "R21") (pin "2") (pinfunction "2_2") (pintype "input"))
      (node (ref "R8") (pin "2") (pinfunction "2_2") (pintype "input"))
      (node (ref "U5") (pin "4") (pinfunction "SDA/SDI/SDO_4") (pintype "unspecified"))
      (node (ref "U6") (pin "4") (pinfunction "SDA/SDI/SDO_4") (pintype "unspecified"))
      (node (ref "U7") (pin "4") (pinfunction "SDA_4") (pintype "unspecified"))
      (node (ref "USB2") (pin "2") (pinfunction "D-_2") (pintype "input"))
    )
    (net (code "10") (name "IO0") (class "Default")
      (node (ref "H1") (pin "2") (pinfunction "2_2") (pintype "input"))
      (node (ref "U1") (pin "25") (pinfunction "IO0_25") (pintype "unspecified"))
    )
    (net (code "11") (name "LED_SIG") (class "Default")
      (node (ref "Q1") (pin "2") (pinfunction "S_2") (pintype "unspecified"))
      (node (ref "R1") (pin "2") (pinfunction "2_2") (pintype "input"))
      (node (ref "U1") (pin "23") (pinfunction "IO15_23") (pintype "unspecified"))
    )
    (net (code "12") (name "MOT_EN") (class "Default")
      (node (ref "U1") (pin "26") (pinfunction "IO4_26") (pintype "unspecified"))
      (node (ref "U3") (pin "1") (pinfunction "EN1_1") (pintype "unspecified"))
      (node (ref "U3") (pin "33") (pinfunction "EN3_33") (pintype "unspecified"))
      (node (ref "U3") (pin "35") (pinfunction "EN2_35") (pintype "unspecified"))
    )
    (net (code "13") (name "MOT_SEN_U") (class "Default")
      (node (ref "R11") (pin "1") (pinfunction "1_1") (pintype "input"))
      (node (ref "R16") (pin "2") (pinfunction "2_2") (pintype "input"))
      (node (ref "R19") (pin "1") (pinfunction "1_1") (pintype "input"))
      (node (ref "U11") (pin "9") (pinfunction "IN3+_9") (pintype "unspecified"))
    )
    (net (code "14") (name "MOT_SEN_U_DIG") (class "Default")
      (node (ref "U1") (pin "8") (pinfunction "IO32_8") (pintype "unspecified"))
      (node (ref "U11") (pin "14") (pinfunction "OUT3_14") (pintype "unspecified"))
    )
    (net (code "15") (name "MOT_SEN_V") (class "Default")
      (node (ref "R12") (pin "1") (pinfunction "1_1") (pintype "input"))
      (node (ref "R14") (pin "2") (pinfunction "2_2") (pintype "input"))
      (node (ref "R17") (pin "1") (pinfunction "1_1") (pintype "input"))
      (node (ref "U11") (pin "7") (pinfunction "IN2+_7") (pintype "unspecified"))
    )
    (net (code "16") (name "MOT_SEN_VIRT") (class "Default")
      (node (ref "R14") (pin "1") (pinfunction "1_1") (pintype "input"))
      (node (ref "R15") (pin "1") (pinfunction "1_1") (pintype "input"))
      (node (ref "R16") (pin "1") (pinfunction "1_1") (pintype "input"))
      (node (ref "U11") (pin "4") (pinfunction "IN1-_4") (pintype "unspecified"))
      (node (ref "U11") (pin "6") (pinfunction "IN2-_6") (pintype "unspecified"))
      (node (ref "U11") (pin "8") (pinfunction "IN3-_8") (pintype "unspecified"))
    )
    (net (code "17") (name "MOT_SEN_V_DIG") (class "Default")
      (node (ref "U1") (pin "9") (pinfunction "IO33_9") (pintype "unspecified"))
      (node (ref "U11") (pin "1") (pinfunction "OUT2_1") (pintype "unspecified"))
    )
    (net (code "18") (name "MOT_SEN_W") (class "Default")
      (node (ref "R13") (pin "1") (pinfunction "1_1") (pintype "input"))
      (node (ref "R15") (pin "2") (pinfunction "2_2") (pintype "input"))
      (node (ref "R18") (pin "1") (pinfunction "1_1") (pintype "input"))
      (node (ref "U11") (pin "5") (pinfunction "IN1+_5") (pintype "unspecified"))
    )
    (net (code "19") (name "MOT_SEN_W_DIG") (class "Default")
      (node (ref "U1") (pin "10") (pinfunction "IO25_10") (pintype "unspecified"))
      (node (ref "U11") (pin "2") (pinfunction "OUT1_2") (pintype "unspecified"))
    )
    (net (code "20") (name "MOT_SIG_U") (class "Default")
      (node (ref "U1") (pin "14") (pinfunction "IO12_14") (pintype "unspecified"))
      (node (ref "U3") (pin "2") (pinfunction "IN1_2") (pintype "unspecified"))
    )
    (net (code "21") (name "MOT_SIG_V") (class "Default")
      (node (ref "U1") (pin "13") (pinfunction "IO14_13") (pintype "unspecified"))
      (node (ref "U3") (pin "36") (pinfunction "IN2_36") (pintype "unspecified"))
    )
    (net (code "22") (name "MOT_SIG_W") (class "Default")
      (node (ref "U1") (pin "16") (pinfunction "IO13_16") (pintype "unspecified"))
      (node (ref "U3") (pin "34") (pinfunction "IN3_34") (pintype "unspecified"))
    )
    (net (code "23") (name "MOT_U") (class "Default")
      (node (ref "R19") (pin "2") (pinfunction "2_2") (pintype "input"))
      (node (ref "U13") (pin "5") (pinfunction "5_5") (pintype "unspecified"))
      (node (ref "U3") (pin "10") (pinfunction "OUT1_10") (pintype "unspecified"))
    )
    (net (code "24") (name "MOT_V") (class "Default")
      (node (ref "R17") (pin "2") (pinfunction "2_2") (pintype "input"))
      (node (ref "U13") (pin "3") (pinfunction "3_3") (pintype "unspecified"))
      (node (ref "U3") (pin "13") (pinfunction "OUT2_13") (pintype "unspecified"))
    )
    (net (code "25") (name "MOT_W") (class "Default")
      (node (ref "R18") (pin "2") (pinfunction "2_2") (pintype "input"))
      (node (ref "U13") (pin "1") (pinfunction "1_1") (pintype "unspecified"))
      (node (ref "U3") (pin "15") (pinfunction "OUT3_15") (pintype "unspecified"))
    )
    (net (code "26") (name "Net-(BUZZER1-+)") (class "Default")
      (node (ref "BUZZER1") (pin "1") (pinfunction "+_1") (pintype "unspecified"))
      (node (ref "C27") (pin "2") (pinfunction "2_2") (pintype "unspecified"))
      (node (ref "Q2") (pin "3") (pinfunction "D_3") (pintype "unspecified"))
    )
    (net (code "27") (name "Net-(D2-A)") (class "Default")
      (node (ref "D2") (pin "2") (pinfunction "A_2") (pintype "unspecified"))
      (node (ref "Q4") (pin "2") (pinfunction "E_2") (pintype "unspecified"))
    )
    (net (code "28") (name "Net-(LED1-DIN)") (class "Default")
      (node (ref "LED1") (pin "1") (pinfunction "DIN_1") (pintype "unspecified"))
      (node (ref "LED2") (pin "3") (pinfunction "DOUT_3") (pintype "unspecified"))
    )
    (net (code "29") (name "Net-(LED2-DIN)") (class "Default")
      (node (ref "LED2") (pin "1") (pinfunction "DIN_1") (pintype "unspecified"))
      (node (ref "Q1") (pin "3") (pinfunction "D_3") (pintype "unspecified"))
      (node (ref "R2") (pin "2") (pinfunction "2_2") (pintype "input"))
    )
    (net (code "30") (name "Net-(Q2-G)") (class "Default")
      (node (ref "Q2") (pin "1") (pinfunction "G_1") (pintype "unspecified"))
      (node (ref "R6") (pin "2") (pinfunction "2_2") (pintype "unspecified"))
    )
    (net (code "31") (name "Net-(Q3-D)") (class "Default")
      (node (ref "Q3") (pin "3") (pinfunction "D_3") (pintype "unspecified"))
      (node (ref "USB2") (pin "1") (pinfunction "VCC_1") (pintype "input"))
    )
    (net (code "32") (name "Net-(Q3-G)") (class "Default")
      (node (ref "Q3") (pin "1") (pinfunction "G_1") (pintype "unspecified"))
      (node (ref "Q4") (pin "3") (pinfunction "C_3") (pintype "unspecified"))
      (node (ref "R9") (pin "1") (pinfunction "1_1") (pintype "unspecified"))
    )
    (net (code "33") (name "Net-(Q4-B)") (class "Default")
      (node (ref "Q4") (pin "1") (pinfunction "B_1") (pintype "unspecified"))
      (node (ref "R10") (pin "1") (pinfunction "1_1") (pintype "input"))
    )
    (net (code "34") (name "Net-(Q5-G)") (class "Default")
      (node (ref "Q5") (pin "1") (pinfunction "G_1") (pintype "unspecified"))
      (node (ref "R20") (pin "1") (pinfunction "1_1") (pintype "unspecified"))
    )
    (net (code "35") (name "Net-(U1-IO21)") (class "Default")
      (node (ref "R21") (pin "1") (pinfunction "1_1") (pintype "input"))
      (node (ref "U1") (pin "33") (pinfunction "IO21_33") (pintype "unspecified"))
    )
    (net (code "36") (name "Net-(U1-IO22)") (class "Default")
      (node (ref "R22") (pin "1") (pinfunction "1_1") (pintype "input"))
      (node (ref "U1") (pin "36") (pinfunction "IO22_36") (pintype "unspecified"))
    )
    (net (code "37") (name "Net-(U3-CPH)") (class "Default")
      (node (ref "C18") (pin "1") (pinfunction "1_1") (pintype "input"))
      (node (ref "U3") (pin "6") (pinfunction "CPH_6") (pintype "unspecified"))
    )
    (net (code "38") (name "Net-(U3-CPL)") (class "Default")
      (node (ref "C18") (pin "2") (pinfunction "2_2") (pintype "input"))
      (node (ref "U3") (pin "5") (pinfunction "CPL_5") (pintype "unspecified"))
    )
    (net (code "39") (name "Net-(U3-V3P3)") (class "Default")
      (node (ref "C30") (pin "1") (pinfunction "1_1") (pintype "unspecified"))
      (node (ref "U3") (pin "25") (pinfunction "V3P3_25") (pintype "unspecified"))
    )
    (net (code "40") (name "Net-(U3-VCP)") (class "Default")
      (node (ref "C19") (pin "2") (pinfunction "2_2") (pintype "unspecified"))
      (node (ref "U3") (pin "7") (pinfunction "VCP_7") (pintype "unspecified"))
    )
    (net (code "41") (name "Net-(U4-CB)") (class "Default")
      (node (ref "C23") (pin "1") (pinfunction "1_1") (pintype "unspecified"))
      (node (ref "U4") (pin "1") (pinfunction "CB_1") (pintype "unspecified"))
    )
    (net (code "42") (name "Net-(U4-FB)") (class "Default")
      (node (ref "R3") (pin "2") (pinfunction "2_2") (pintype "unspecified"))
      (node (ref "R4") (pin "2") (pinfunction "2_2") (pintype "input"))
      (node (ref "U4") (pin "3") (pinfunction "FB_3") (pintype "unspecified"))
    )
    (net (code "43") (name "Net-(U4-SW)") (class "Default")
      (node (ref "C23") (pin "2") (pinfunction "2_2") (pintype "unspecified"))
      (node (ref "L1") (pin "1") (pinfunction "1_1") (pintype "unspecified"))
      (node (ref "U4") (pin "6") (pinfunction "SW_6") (pintype "unspecified"))
    )
    (net (code "44") (name "Net-(U10-A)") (class "Default")
      (node (ref "C25") (pin "1") (pinfunction "1_1") (pintype "input"))
      (node (ref "C26") (pin "1") (pinfunction "1_1") (pintype "input"))
      (node (ref "R5") (pin "2") (pinfunction "2_2") (pintype "unspecified"))
      (node (ref "U10") (pin "2") (pinfunction "A_2") (pintype "unspecified"))
      (node (ref "U9") (pin "2") (pinfunction "A_2") (pintype "unspecified"))
    )
    (net (code "45") (name "RXD") (class "Default")
      (node (ref "H1") (pin "4") (pinfunction "4_4") (pintype "input"))
      (node (ref "U1") (pin "34") (pinfunction "RXD0_34") (pintype "unspecified"))
    )
    (net (code "46") (name "TXD") (class "Default")
      (node (ref "H1") (pin "3") (pinfunction "3_3") (pintype "input"))
      (node (ref "U1") (pin "35") (pinfunction "TXD0_35") (pintype "unspecified"))
    )
    (net (code "47") (name "VIN") (class "Default")
      (node (ref "CN1") (pin "2") (pinfunction "2_2") (pintype "unspecified"))
      (node (ref "Q5") (pin "2") (pinfunction "S_2") (pintype "unspecified"))
    )
    (net (code "48") (name "VIN_F") (class "Default")
      (node (ref "C15") (pin "1") (pinfunction "1_1") (pintype "unspecified"))
      (node (ref "C17") (pin "2") (pinfunction "2_2") (pintype "unspecified"))
      (node (ref "C19") (pin "1") (pinfunction "1_1") (pintype "unspecified"))
      (node (ref "C31") (pin "2") (pinfunction "2_2") (pintype "unspecified"))
      (node (ref "C32") (pin "1") (pinfunction "1_1") (pintype "input"))
      (node (ref "F5") (pin "2") (pinfunction "2_2") (pintype "unspecified"))
      (node (ref "F6") (pin "2") (pinfunction "2_2") (pintype "unspecified"))
      (node (ref "R25") (pin "2") (pinfunction "2_2") (pintype "input"))
      (node (ref "R9") (pin "2") (pinfunction "2_2") (pintype "unspecified"))
      (node (ref "U3") (pin "19") (pinfunction "VM_19") (pintype "unspecified"))
      (node (ref "U3") (pin "9") (pinfunction "VM_9") (pintype "unspecified"))
      (node (ref "U4") (pin "4") (pinfunction "EN_4") (pintype "unspecified"))
      (node (ref "U4") (pin "5") (pinfunction "VIN_5") (pintype "unspecified"))
    )
    (net (code "49") (name "VIN_REV_PROT") (class "Default")
      (node (ref "D2") (pin "1") (pinfunction "K_1") (pintype "unspecified"))
      (node (ref "F5") (pin "1") (pinfunction "1_1") (pintype "unspecified"))
      (node (ref "F6") (pin "1") (pinfunction "1_1") (pintype "unspecified"))
      (node (ref "Q3") (pin "2") (pinfunction "S_2") (pintype "unspecified"))
      (node (ref "Q5") (pin "3") (pinfunction "D_3") (pintype "unspecified"))
    )
    (net (code "50") (name "VIN_SEN") (class "Default")
      (node (ref "R24") (pin "2") (pinfunction "2_2") (pintype "input"))
      (node (ref "R25") (pin "1") (pinfunction "1_1") (pintype "input"))
      (node (ref "U1") (pin "7") (pinfunction "IO35_7") (pintype "unspecified"))
    )
    (net (code "51") (name "unconnected-(LED1-DOUT-Pad3)") (class "Default")
      (node (ref "LED1") (pin "3") (pinfunction "DOUT_3") (pintype "unspecified+no_connect"))
    )
    (net (code "52") (name "unconnected-(SW1-Pad2)") (class "Default")
      (node (ref "SW1") (pin "2") (pinfunction "2_2") (pintype "unspecified"))
    )
    (net (code "53") (name "unconnected-(SW1-Pad4)") (class "Default")
      (node (ref "SW1") (pin "4") (pinfunction "4_4") (pintype "unspecified"))
    )
    (net (code "54") (name "unconnected-(U1-IO2-Pad24)") (class "Default")
      (node (ref "U1") (pin "24") (pinfunction "IO2_24") (pintype "unspecified"))
    )
    (net (code "55") (name "unconnected-(U1-IO5-Pad29)") (class "Default")
      (node (ref "U1") (pin "29") (pinfunction "IO5_29") (pintype "unspecified"))
    )
    (net (code "56") (name "unconnected-(U1-IO17-Pad28)") (class "Default")
      (node (ref "U1") (pin "28") (pinfunction "IO17_28") (pintype "unspecified"))
    )
    (net (code "57") (name "unconnected-(U1-IO18-Pad30)") (class "Default")
      (node (ref "U1") (pin "30") (pinfunction "IO18_30") (pintype "unspecified"))
    )
    (net (code "58") (name "unconnected-(U1-IO19-Pad31)") (class "Default")
      (node (ref "U1") (pin "31") (pinfunction "IO19_31") (pintype "unspecified"))
    )
    (net (code "59") (name "unconnected-(U1-IO23-Pad37)") (class "Default")
      (node (ref "U1") (pin "37") (pinfunction "IO23_37") (pintype "unspecified"))
    )
    (net (code "60") (name "unconnected-(U1-IO26-Pad11)") (class "Default")
      (node (ref "U1") (pin "11") (pinfunction "IO26_11") (pintype "unspecified"))
    )
    (net (code "61") (name "unconnected-(U1-NC-Pad17)") (class "Default")
      (node (ref "U1") (pin "17") (pinfunction "NC_17") (pintype "unspecified+no_connect"))
    )
    (net (code "62") (name "unconnected-(U1-NC-Pad18)") (class "Default")
      (node (ref "U1") (pin "18") (pinfunction "NC_18") (pintype "unspecified+no_connect"))
    )
    (net (code "63") (name "unconnected-(U1-NC-Pad19)") (class "Default")
      (node (ref "U1") (pin "19") (pinfunction "NC_19") (pintype "unspecified+no_connect"))
    )
    (net (code "64") (name "unconnected-(U1-NC-Pad20)") (class "Default")
      (node (ref "U1") (pin "20") (pinfunction "NC_20") (pintype "unspecified+no_connect"))
    )
    (net (code "65") (name "unconnected-(U1-NC-Pad21)") (class "Default")
      (node (ref "U1") (pin "21") (pinfunction "NC_21") (pintype "unspecified+no_connect"))
    )
    (net (code "66") (name "unconnected-(U1-NC-Pad22)") (class "Default")
      (node (ref "U1") (pin "22") (pinfunction "NC_22") (pintype "unspecified+no_connect"))
    )
    (net (code "67") (name "unconnected-(U1-NC-Pad32)") (class "Default")
      (node (ref "U1") (pin "32") (pinfunction "NC_32") (pintype "unspecified+no_connect"))
    )
    (net (code "68") (name "unconnected-(U1-SENSOR_VN-Pad5)") (class "Default")
      (node (ref "U1") (pin "5") (pinfunction "SENSOR_VN_5") (pintype "unspecified"))
    )
    (net (code "69") (name "unconnected-(U1-SENSOR_VP-Pad4)") (class "Default")
      (node (ref "U1") (pin "4") (pinfunction "SENSOR_VP_4") (pintype "unspecified"))
    )
    (net (code "70") (name "unconnected-(U3-NC-Pad4)") (class "Default")
      (node (ref "U3") (pin "4") (pinfunction "NC_4") (pintype "unspecified+no_connect"))
    )
    (net (code "71") (name "unconnected-(U3-NC-Pad8)") (class "Default")
      (node (ref "U3") (pin "8") (pinfunction "NC_8") (pintype "unspecified+no_connect"))
    )
    (net (code "72") (name "unconnected-(U3-NC-Pad14)") (class "Default")
      (node (ref "U3") (pin "14") (pinfunction "NC_14") (pintype "unspecified+no_connect"))
    )
    (net (code "73") (name "unconnected-(U3-RSVD-Pad18)") (class "Default")
      (node (ref "U3") (pin "18") (pinfunction "RSVD_18") (pintype "unspecified+no_connect"))
    )
    (net (code "74") (name "unconnected-(U3-nCOMPO-Pad29)") (class "Default")
      (node (ref "U3") (pin "29") (pinfunction "nCOMPO_29") (pintype "unspecified"))
    )
    (net (code "75") (name "unconnected-(U3-nFAULT-Pad28)") (class "Default")
      (node (ref "U3") (pin "28") (pinfunction "nFAULT_28") (pintype "unspecified"))
    )
    (net (code "76") (name "unconnected-(U3-nRESET-Pad26)") (class "Default")
      (node (ref "U3") (pin "26") (pinfunction "nRESET_26") (pintype "unspecified"))
    )
    (net (code "77") (name "unconnected-(U3-nSLEEP-Pad27)") (class "Default")
      (node (ref "U3") (pin "27") (pinfunction "nSLEEP_27") (pintype "unspecified"))
    )
    (net (code "78") (name "unconnected-(U5-INT_DRDY-Pad7)") (class "Default")
      (node (ref "U5") (pin "7") (pinfunction "INT_DRDY_7") (pintype "unspecified+no_connect"))
    )
    (net (code "79") (name "unconnected-(U6-INT_DRDY-Pad7)") (class "Default")
      (node (ref "U6") (pin "7") (pinfunction "INT_DRDY_7") (pintype "unspecified+no_connect"))
    )
    (net (code "80") (name "unconnected-(U7-NC-Pad1)") (class "Default")
      (node (ref "U7") (pin "1") (pinfunction "NC_1") (pintype "unspecified+no_connect"))
    )
    (net (code "81") (name "unconnected-(U7-NC-Pad6)") (class "Default")
      (node (ref "U7") (pin "6") (pinfunction "NC_6") (pintype "unspecified+no_connect"))
    )
    (net (code "82") (name "unconnected-(U13-Pad2)") (class "Default")
      (node (ref "U13") (pin "2") (pinfunction "2_2") (pintype "unspecified"))
    )
    (net (code "83") (name "unconnected-(U13-Pad4)") (class "Default")
      (node (ref "U13") (pin "4") (pinfunction "4_4") (pintype "unspecified"))
    )
    (net (code "84") (name "unconnected-(U13-Pad6)") (class "Default")
      (node (ref "U13") (pin "6") (pinfunction "6_6") (pintype "unspecified"))
    )
  )
)
